# Janus_v2.net
KiCad netlist of a schematic drawn in EAGLE
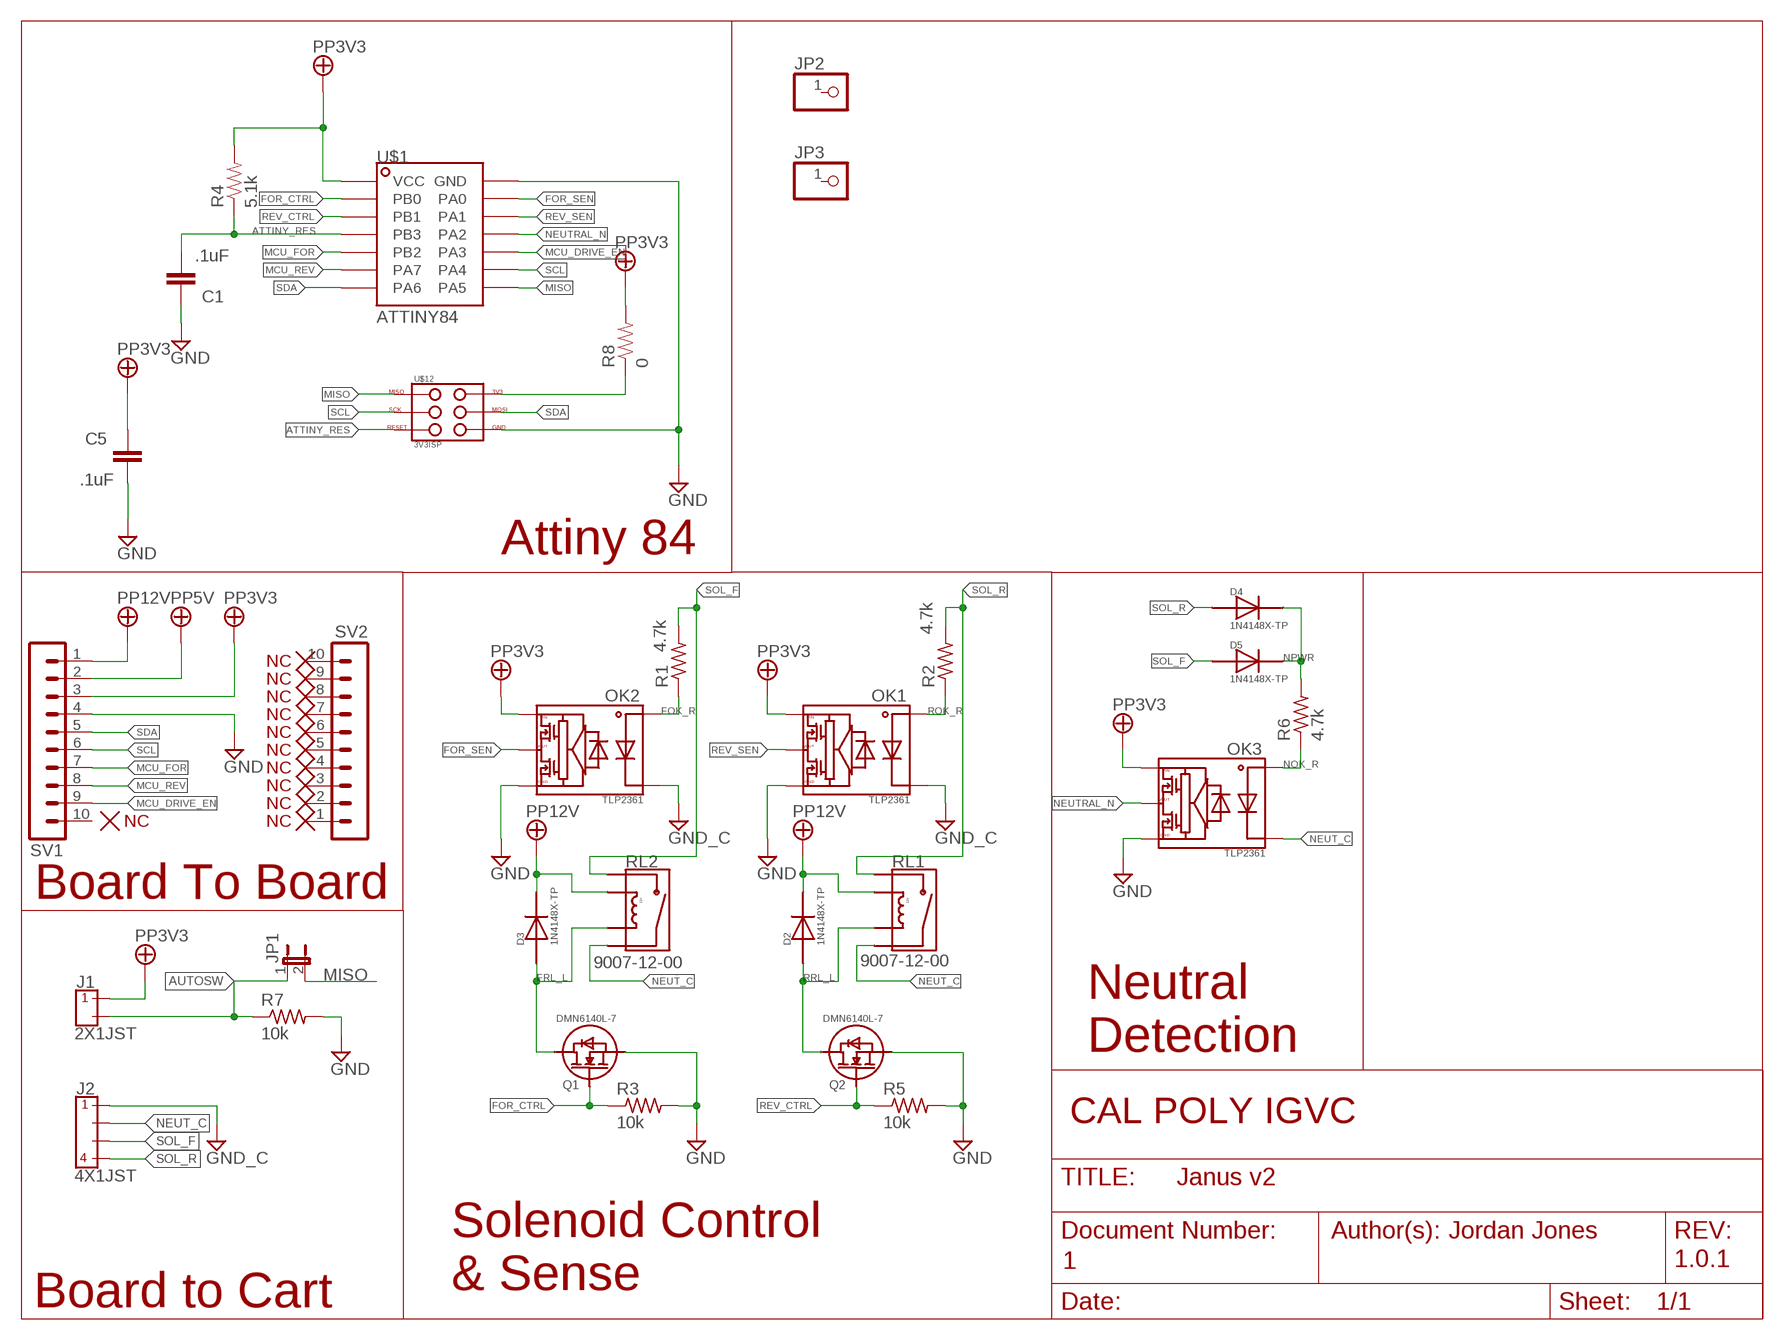
[diagram p0: schematic, sheet 1]

(export (version "E")
  (design (tool "Eeschema 10.0.6"))
  (components
    (comp (ref "C1")
      (value ".1uF")
      (footprint "eagle-import:C0603")
      (libsource (lib "eagle-import") (part "C-EUC0603"))
    )
    (comp (ref "C5")
      (value ".1uF")
      (footprint "eagle-import:C0603")
      (libsource (lib "eagle-import") (part "C-EUC0603"))
    )
    (comp (ref "D2")
      (value "1N4148X-TP")
      (footprint "eagle-import:SOD523_SC79")
      (fields (field (name "DIGIKEYPART") "1N4148XTPMSCT-ND"))
      (libsource (lib "eagle-import") (part "1N4148X-TP"))
    )
    (comp (ref "D3")
      (value "1N4148X-TP")
      (footprint "eagle-import:SOD523_SC79")
      (fields (field (name "DIGIKEYPART") "1N4148XTPMSCT-ND"))
      (libsource (lib "eagle-import") (part "1N4148X-TP"))
    )
    (comp (ref "D4")
      (value "1N4148X-TP")
      (footprint "eagle-import:SOD523_SC79")
      (fields (field (name "DIGIKEYPART") "1N4148XTPMSCT-ND"))
      (libsource (lib "eagle-import") (part "1N4148X-TP"))
    )
    (comp (ref "D5")
      (value "1N4148X-TP")
      (footprint "eagle-import:SOD523_SC79")
      (fields (field (name "DIGIKEYPART") "1N4148XTPMSCT-ND"))
      (libsource (lib "eagle-import") (part "1N4148X-TP"))
    )
    (comp (ref "J1")
      (value "2X1JST")
      (footprint "eagle-import:JST-2-PTH-VERT")
      (fields (field (name "DIGIKEYPART") "455-1704-ND"))
      (libsource (lib "eagle-import") (part "2X1JST"))
    )
    (comp (ref "J2")
      (value "4X1JST")
      (footprint "eagle-import:JST-4-PTH-VERT")
      (fields (field (name "DIGIKEYPART") "455-1706-ND"))
      (libsource (lib "eagle-import") (part "4X1JST"))
    )
    (comp (ref "JP1")
      (value "JP1E")
      (footprint "eagle-import:JP1")
      (libsource (lib "eagle-import") (part "JP1E"))
    )
    (comp (ref "JP2")
      (value "PINHD-1X1")
      (footprint "eagle-import:1X01")
      (libsource (lib "eagle-import") (part "PINHD-1X1"))
    )
    (comp (ref "JP3")
      (value "PINHD-1X1")
      (footprint "eagle-import:1X01")
      (libsource (lib "eagle-import") (part "PINHD-1X1"))
    )
    (comp (ref "OK1")
      (value "TLP2361")
      (footprint "eagle-import:SOIC-6-5")
      (fields (field (name "DIGIKEYPART") "TLP2361(TPLECT-ND"))
      (libsource (lib "eagle-import") (part "TLP2361"))
    )
    (comp (ref "OK2")
      (value "TLP2361")
      (footprint "eagle-import:SOIC-6-5")
      (fields (field (name "DIGIKEYPART") "TLP2361(TPLECT-ND"))
      (libsource (lib "eagle-import") (part "TLP2361"))
    )
    (comp (ref "OK3")
      (value "TLP2361")
      (footprint "eagle-import:SOIC-6-5")
      (fields (field (name "DIGIKEYPART") "TLP2361(TPLECT-ND"))
      (libsource (lib "eagle-import") (part "TLP2361"))
    )
    (comp (ref "Q1")
      (value "DMN6140L-7")
      (footprint "eagle-import:SOT-23-3")
      (fields (field (name "DIGIKEYPART") "DMN6140L-7DICT-ND"))
      (libsource (lib "eagle-import") (part "DMN6140L-7"))
    )
    (comp (ref "Q2")
      (value "DMN6140L-7")
      (footprint "eagle-import:SOT-23-3")
      (fields (field (name "DIGIKEYPART") "DMN6140L-7DICT-ND"))
      (libsource (lib "eagle-import") (part "DMN6140L-7"))
    )
    (comp (ref "R1")
      (value "4.7k")
      (footprint "eagle-import:R0805")
      (libsource (lib "eagle-import") (part "R-US_R0805"))
    )
    (comp (ref "R2")
      (value "4.7k")
      (footprint "eagle-import:R0805")
      (libsource (lib "eagle-import") (part "R-US_R0805"))
    )
    (comp (ref "R3")
      (value "10k")
      (footprint "eagle-import:R0603")
      (libsource (lib "eagle-import") (part "R-US_R0603"))
    )
    (comp (ref "R4")
      (value "5.1k")
      (footprint "eagle-import:0603-RES")
      (libsource (lib "eagle-import") (part "RESISTOR0603"))
    )
    (comp (ref "R5")
      (value "10k")
      (footprint "eagle-import:R0603")
      (libsource (lib "eagle-import") (part "R-US_R0603"))
    )
    (comp (ref "R6")
      (value "4.7k")
      (footprint "eagle-import:R0805")
      (libsource (lib "eagle-import") (part "R-US_R0805"))
    )
    (comp (ref "R7")
      (value "10k")
      (footprint "eagle-import:R0603")
      (libsource (lib "eagle-import") (part "R-US_R0603"))
    )
    (comp (ref "R8")
      (value "0")
      (footprint "eagle-import:0603-RES")
      (libsource (lib "eagle-import") (part "RESISTOR0603"))
    )
    (comp (ref "RL1")
      (value "9007-12-00")
      (footprint "eagle-import:RELAY9007")
      (fields (field (name "COILVOLTAGE") "12v") (field (name "DIGIKEYPART") "306-1064-ND"))
      (libsource (lib "eagle-import") (part "9007-12-00"))
    )
    (comp (ref "RL2")
      (value "9007-12-00")
      (footprint "eagle-import:RELAY9007")
      (fields (field (name "COILVOLTAGE") "12v") (field (name "DIGIKEYPART") "306-1064-ND"))
      (libsource (lib "eagle-import") (part "9007-12-00"))
    )
    (comp (ref "SV1")
      (value "MA10-1")
      (footprint "eagle-import:MA10-1")
      (libsource (lib "eagle-import") (part "MA10-1"))
    )
    (comp (ref "SV2")
      (value "MA10-1")
      (footprint "eagle-import:MA10-1")
      (libsource (lib "eagle-import") (part "MA10-1"))
    )
    (comp (ref "U$1")
      (value "ATTINY84")
      (footprint "eagle-import:SOIC-14")
      (fields (field (name "DIGIKEYPART") "ATTINY84A-SSU-ND"))
      (libsource (lib "eagle-import") (part "ATTINY84"))
    )
    (comp (ref "U$12")
      (value "3V3ISP")
      (footprint "eagle-import:3X2SMD")
      (fields (field (name "DIGIKEYPART") "WM17457-ND"))
      (libsource (lib "eagle-import") (part "3V3ISP"))
    )
  )
  (nets
    (net (code "1") (name "/FOK_R") (class "Default")
      (node (ref "OK2") (pin "P$1") (pinfunction "P$1_P$1") (pintype "bidirectional"))
      (node (ref "R1") (pin "1") (pinfunction "1_1") (pintype "passive"))
    )
    (net (code "2") (name "/FRL_L") (class "Default")
      (node (ref "D3") (pin "P$1") (pinfunction "P$1_P$1") (pintype "bidirectional"))
      (node (ref "Q1") (pin "P$3") (pinfunction "D_P$3") (pintype "bidirectional"))
      (node (ref "RL2") (pin "P$3") (pinfunction "COILB_P$3") (pintype "bidirectional"))
    )
    (net (code "3") (name "/NOK_R") (class "Default")
      (node (ref "OK3") (pin "P$1") (pinfunction "P$1_P$1") (pintype "bidirectional"))
      (node (ref "R6") (pin "1") (pinfunction "1_1") (pintype "passive"))
    )
    (net (code "4") (name "/NPWR") (class "Default")
      (node (ref "D4") (pin "P$2") (pinfunction "P$2_P$2") (pintype "bidirectional"))
      (node (ref "D5") (pin "P$2") (pinfunction "P$2_P$2") (pintype "bidirectional"))
      (node (ref "R6") (pin "2") (pinfunction "2_2") (pintype "passive"))
    )
    (net (code "5") (name "/ROK_R") (class "Default")
      (node (ref "OK1") (pin "P$1") (pinfunction "P$1_P$1") (pintype "bidirectional"))
      (node (ref "R2") (pin "1") (pinfunction "1_1") (pintype "passive"))
    )
    (net (code "6") (name "/RRL_L") (class "Default")
      (node (ref "D2") (pin "P$1") (pinfunction "P$1_P$1") (pintype "bidirectional"))
      (node (ref "Q2") (pin "P$3") (pinfunction "D_P$3") (pintype "bidirectional"))
      (node (ref "RL1") (pin "P$3") (pinfunction "COILB_P$3") (pintype "bidirectional"))
    )
    (net (code "7") (name "ATTINY_RES") (class "Default")
      (node (ref "C1") (pin "2") (pinfunction "2_2") (pintype "passive"))
      (node (ref "R4") (pin "1") (pinfunction "1_1") (pintype "passive"))
      (node (ref "U$1") (pin "P$4") (pinfunction "PB3_P$4") (pintype "bidirectional"))
      (node (ref "U$12") (pin "P$3") (pinfunction "P$3_P$3") (pintype "bidirectional"))
    )
    (net (code "8") (name "AUTOSW") (class "Default")
      (node (ref "J1") (pin "2") (pinfunction "P$2_2") (pintype "bidirectional"))
      (node (ref "JP1") (pin "1") (pinfunction "1_1") (pintype "passive"))
      (node (ref "R7") (pin "1") (pinfunction "1_1") (pintype "passive"))
    )
    (net (code "9") (name "FOR_CTRL") (class "Default")
      (node (ref "Q1") (pin "P$1") (pinfunction "G_P$1") (pintype "bidirectional"))
      (node (ref "R3") (pin "1") (pinfunction "1_1") (pintype "passive"))
      (node (ref "U$1") (pin "P$2") (pinfunction "PB0_P$2") (pintype "bidirectional"))
    )
    (net (code "10") (name "FOR_SEN") (class "Default")
      (node (ref "OK2") (pin "P$5") (pinfunction "P$5_P$5") (pintype "bidirectional"))
      (node (ref "U$1") (pin "P$13") (pinfunction "PA0_P$13") (pintype "bidirectional"))
    )
    (net (code "11") (name "GND") (class "Default")
      (node (ref "C1") (pin "1") (pinfunction "1_1") (pintype "passive"))
      (node (ref "C5") (pin "2") (pinfunction "2_2") (pintype "passive"))
      (node (ref "OK1") (pin "P$4") (pinfunction "P$4_P$4") (pintype "bidirectional"))
      (node (ref "OK2") (pin "P$4") (pinfunction "P$4_P$4") (pintype "bidirectional"))
      (node (ref "OK3") (pin "P$4") (pinfunction "P$4_P$4") (pintype "bidirectional"))
      (node (ref "Q1") (pin "P$2") (pinfunction "S_P$2") (pintype "bidirectional"))
      (node (ref "Q2") (pin "P$2") (pinfunction "S_P$2") (pintype "bidirectional"))
      (node (ref "R3") (pin "2") (pinfunction "2_2") (pintype "passive"))
      (node (ref "R5") (pin "2") (pinfunction "2_2") (pintype "passive"))
      (node (ref "R7") (pin "2") (pinfunction "2_2") (pintype "passive"))
      (node (ref "SV1") (pin "4") (pinfunction "4_4") (pintype "passive"))
      (node (ref "U$1") (pin "P$14") (pinfunction "GND_P$14") (pintype "bidirectional"))
      (node (ref "U$12") (pin "P$4") (pinfunction "P$4_P$4") (pintype "bidirectional"))
    )
    (net (code "12") (name "GND_C") (class "Default")
      (node (ref "J2") (pin "1") (pinfunction "P$1_1") (pintype "bidirectional"))
      (node (ref "OK1") (pin "P$3") (pinfunction "P$2_P$3") (pintype "bidirectional"))
      (node (ref "OK2") (pin "P$3") (pinfunction "P$2_P$3") (pintype "bidirectional"))
    )
    (net (code "13") (name "MCU_DRIVE_EN") (class "Default")
      (node (ref "SV1") (pin "9") (pinfunction "9_9") (pintype "passive"))
      (node (ref "U$1") (pin "P$10") (pinfunction "PA3_P$10") (pintype "bidirectional"))
    )
    (net (code "14") (name "MCU_FOR") (class "Default")
      (node (ref "SV1") (pin "7") (pinfunction "7_7") (pintype "passive"))
      (node (ref "U$1") (pin "P$5") (pinfunction "PB2_P$5") (pintype "bidirectional"))
    )
    (net (code "15") (name "MCU_REV") (class "Default")
      (node (ref "SV1") (pin "8") (pinfunction "8_8") (pintype "passive"))
      (node (ref "U$1") (pin "P$6") (pinfunction "PA7_P$6") (pintype "bidirectional"))
    )
    (net (code "16") (name "MISO") (class "Default")
      (node (ref "JP1") (pin "2") (pinfunction "2_2") (pintype "passive"))
      (node (ref "U$1") (pin "P$8") (pinfunction "PA5_P$8") (pintype "bidirectional"))
      (node (ref "U$12") (pin "P$1") (pinfunction "P$1_P$1") (pintype "bidirectional"))
    )
    (net (code "17") (name "NEUTRAL_N") (class "Default")
      (node (ref "OK3") (pin "P$5") (pinfunction "P$5_P$5") (pintype "bidirectional"))
      (node (ref "U$1") (pin "P$11") (pinfunction "PA2_P$11") (pintype "bidirectional"))
    )
    (net (code "18") (name "NEUT_C") (class "Default")
      (node (ref "J2") (pin "2") (pinfunction "P$2_2") (pintype "bidirectional"))
      (node (ref "OK3") (pin "P$3") (pinfunction "P$2_P$3") (pintype "bidirectional"))
      (node (ref "RL1") (pin "P$4") (pinfunction "SIGB_P$4") (pintype "bidirectional"))
      (node (ref "RL2") (pin "P$4") (pinfunction "SIGB_P$4") (pintype "bidirectional"))
    )
    (net (code "19") (name "Net-(R8-Pad1)") (class "Default")
      (node (ref "R8") (pin "1") (pinfunction "1_1") (pintype "passive"))
      (node (ref "U$12") (pin "P$6") (pinfunction "P$6_P$6") (pintype "bidirectional"))
    )
    (net (code "20") (name "PP3V3") (class "Default")
      (node (ref "C5") (pin "1") (pinfunction "1_1") (pintype "passive"))
      (node (ref "J1") (pin "1") (pinfunction "P$1_1") (pintype "bidirectional"))
      (node (ref "OK1") (pin "P$6") (pinfunction "P$6_P$6") (pintype "bidirectional"))
      (node (ref "OK2") (pin "P$6") (pinfunction "P$6_P$6") (pintype "bidirectional"))
      (node (ref "OK3") (pin "P$6") (pinfunction "P$6_P$6") (pintype "bidirectional"))
      (node (ref "R4") (pin "2") (pinfunction "2_2") (pintype "passive"))
      (node (ref "R8") (pin "2") (pinfunction "2_2") (pintype "passive"))
      (node (ref "SV1") (pin "3") (pinfunction "3_3") (pintype "passive"))
      (node (ref "U$1") (pin "P$1") (pinfunction "VCC_P$1") (pintype "bidirectional"))
    )
    (net (code "21") (name "PP5V") (class "Default")
      (node (ref "SV1") (pin "2") (pinfunction "2_2") (pintype "passive"))
    )
    (net (code "22") (name "PP12V") (class "Default")
      (node (ref "D2") (pin "P$2") (pinfunction "P$2_P$2") (pintype "bidirectional"))
      (node (ref "D3") (pin "P$2") (pinfunction "P$2_P$2") (pintype "bidirectional"))
      (node (ref "RL1") (pin "P$2") (pinfunction "COILA_P$2") (pintype "bidirectional"))
      (node (ref "RL2") (pin "P$2") (pinfunction "COILA_P$2") (pintype "bidirectional"))
      (node (ref "SV1") (pin "1") (pinfunction "1_1") (pintype "passive"))
    )
    (net (code "23") (name "REV_CTRL") (class "Default")
      (node (ref "Q2") (pin "P$1") (pinfunction "G_P$1") (pintype "bidirectional"))
      (node (ref "R5") (pin "1") (pinfunction "1_1") (pintype "passive"))
      (node (ref "U$1") (pin "P$3") (pinfunction "PB1_P$3") (pintype "bidirectional"))
    )
    (net (code "24") (name "REV_SEN") (class "Default")
      (node (ref "OK1") (pin "P$5") (pinfunction "P$5_P$5") (pintype "bidirectional"))
      (node (ref "U$1") (pin "P$12") (pinfunction "PA1_P$12") (pintype "bidirectional"))
    )
    (net (code "25") (name "SCL") (class "Default")
      (node (ref "SV1") (pin "6") (pinfunction "6_6") (pintype "passive"))
      (node (ref "U$1") (pin "P$9") (pinfunction "PA4_P$9") (pintype "bidirectional"))
      (node (ref "U$12") (pin "P$2") (pinfunction "P$2_P$2") (pintype "bidirectional"))
    )
    (net (code "26") (name "SDA") (class "Default")
      (node (ref "SV1") (pin "5") (pinfunction "5_5") (pintype "passive"))
      (node (ref "U$1") (pin "P$7") (pinfunction "PA6_P$7") (pintype "bidirectional"))
      (node (ref "U$12") (pin "P$5") (pinfunction "P$5_P$5") (pintype "bidirectional"))
    )
    (net (code "27") (name "SOL_F") (class "Default")
      (node (ref "D5") (pin "P$1") (pinfunction "P$1_P$1") (pintype "bidirectional"))
      (node (ref "J2") (pin "3") (pinfunction "P$3_3") (pintype "bidirectional"))
      (node (ref "R1") (pin "2") (pinfunction "2_2") (pintype "passive"))
      (node (ref "RL2") (pin "P$1") (pinfunction "SIGA_P$1") (pintype "bidirectional"))
    )
    (net (code "28") (name "SOL_R") (class "Default")
      (node (ref "D4") (pin "P$1") (pinfunction "P$1_P$1") (pintype "bidirectional"))
      (node (ref "J2") (pin "4") (pinfunction "P$4_4") (pintype "bidirectional"))
      (node (ref "R2") (pin "2") (pinfunction "2_2") (pintype "passive"))
      (node (ref "RL1") (pin "P$1") (pinfunction "SIGA_P$1") (pintype "bidirectional"))
    )
    (net (code "29") (name "unconnected-(JP2-Pad1)") (class "Default")
      (node (ref "JP2") (pin "1") (pinfunction "1_1") (pintype "passive"))
    )
    (net (code "30") (name "unconnected-(JP3-Pad1)") (class "Default")
      (node (ref "JP3") (pin "1") (pinfunction "1_1") (pintype "passive"))
    )
    (net (code "31") (name "unconnected-(SV1-Pad10)") (class "Default")
      (node (ref "SV1") (pin "10") (pinfunction "10_10") (pintype "passive"))
    )
    (net (code "32") (name "unconnected-(SV2-Pad1)") (class "Default")
      (node (ref "SV2") (pin "1") (pinfunction "1_1") (pintype "passive"))
    )
    (net (code "33") (name "unconnected-(SV2-Pad2)") (class "Default")
      (node (ref "SV2") (pin "2") (pinfunction "2_2") (pintype "passive"))
    )
    (net (code "34") (name "unconnected-(SV2-Pad3)") (class "Default")
      (node (ref "SV2") (pin "3") (pinfunction "3_3") (pintype "passive"))
    )
    (net (code "35") (name "unconnected-(SV2-Pad4)") (class "Default")
      (node (ref "SV2") (pin "4") (pinfunction "4_4") (pintype "passive"))
    )
    (net (code "36") (name "unconnected-(SV2-Pad5)") (class "Default")
      (node (ref "SV2") (pin "5") (pinfunction "5_5") (pintype "passive"))
    )
    (net (code "37") (name "unconnected-(SV2-Pad6)") (class "Default")
      (node (ref "SV2") (pin "6") (pinfunction "6_6") (pintype "passive"))
    )
    (net (code "38") (name "unconnected-(SV2-Pad7)") (class "Default")
      (node (ref "SV2") (pin "7") (pinfunction "7_7") (pintype "passive"))
    )
    (net (code "39") (name "unconnected-(SV2-Pad8)") (class "Default")
      (node (ref "SV2") (pin "8") (pinfunction "8_8") (pintype "passive"))
    )
    (net (code "40") (name "unconnected-(SV2-Pad9)") (class "Default")
      (node (ref "SV2") (pin "9") (pinfunction "9_9") (pintype "passive"))
    )
    (net (code "41") (name "unconnected-(SV2-Pad10)") (class "Default")
      (node (ref "SV2") (pin "10") (pinfunction "10_10") (pintype "passive"))
    )
  )
)
